# Humidifier.net
KiCad netlist of a schematic drawn in Altium Designer
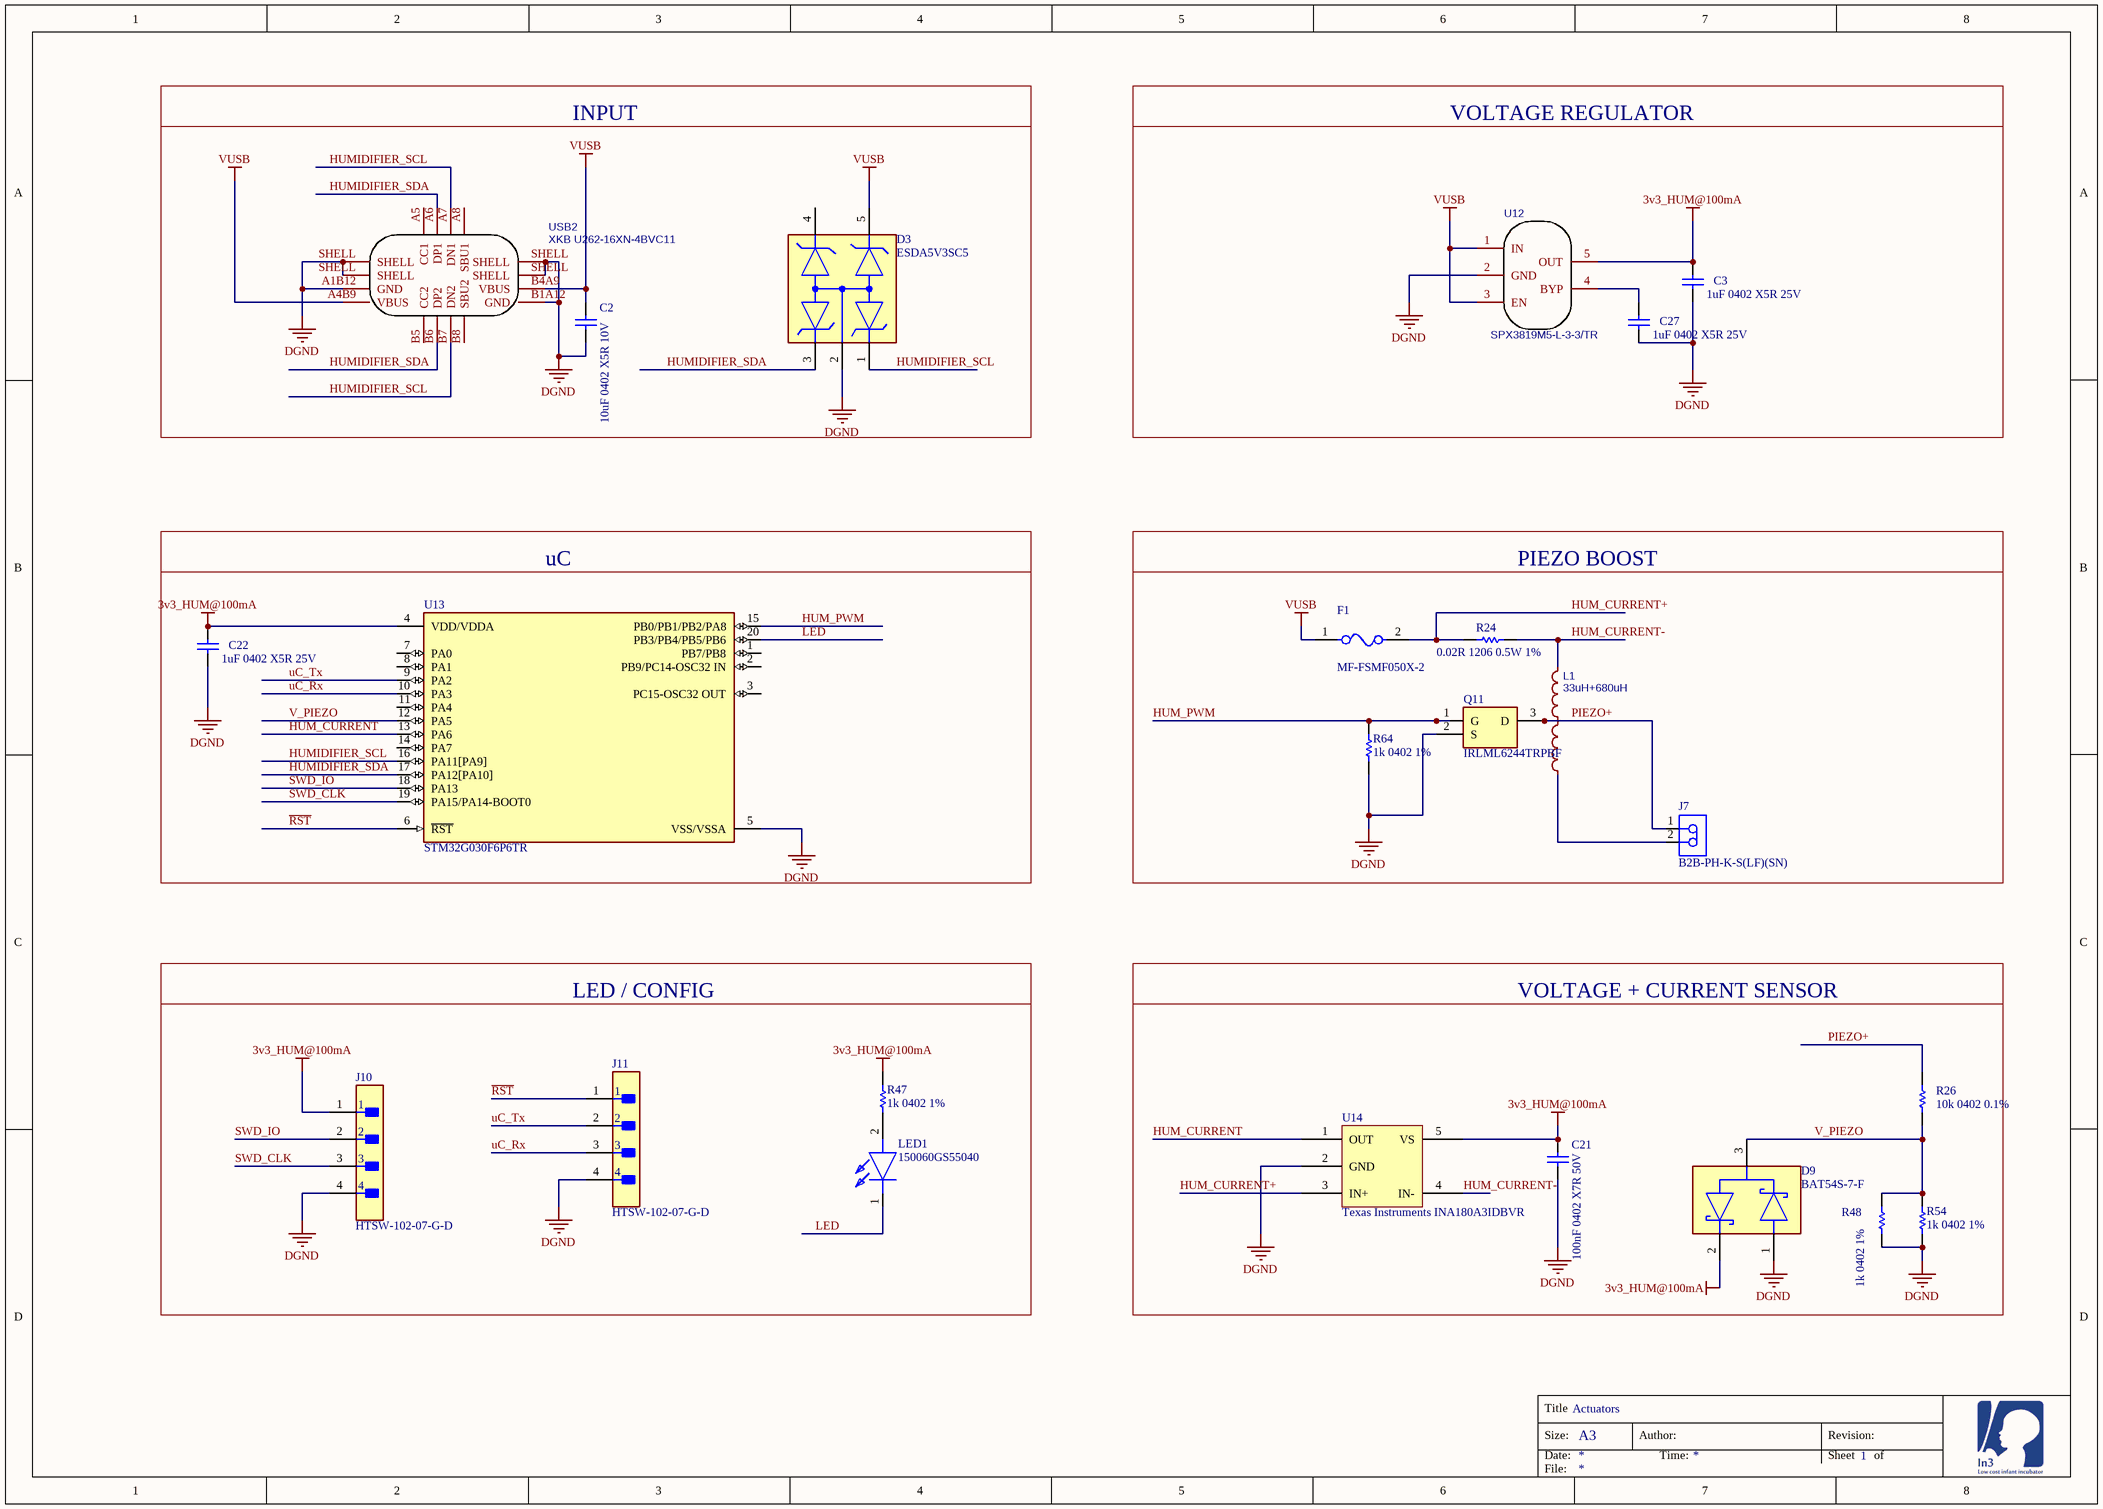
[diagram p0: Humidifier.SchDoc]

(export (version "E")
  (design (tool "Eeschema 10.0.6"))
  (components
    (comp (ref "C2")
      (value "10uF 0402 X5R 10V")
      (footprint "CAPC1005X55X25NL5T10")
      (libsource (lib "Altium Content Vault") (part "CAP-NP-2"))
    )
    (comp (ref "C3")
      (value "1uF 0402 X5R 25V")
      (footprint "CAPC1005X55X25NL5T10")
      (libsource (lib "Altium Content Vault") (part "CAP-NP-2"))
    )
    (comp (ref "C21")
      (value "100nF 0402 X7R 50V")
      (footprint "CAPC1005X55X25NL5T10")
      (libsource (lib "Altium Content Vault") (part "CAP-NP-2"))
    )
    (comp (ref "C22")
      (value "1uF 0402 X5R 25V")
      (footprint "CAPC1005X55X25NL5T10")
      (libsource (lib "Altium Content Vault") (part "CAP-NP-2"))
    )
    (comp (ref "C27")
      (value "1uF 0402 X5R 25V")
      (footprint "CAPC1005X55X25NL5T10")
      (libsource (lib "Altium Content Vault") (part "CAP-NP-2"))
    )
    (comp (ref "D3")
      (value "ESDA5V3SC5")
      (footprint "FP-SOT23-5L-MFG")
      (description "TVS DIODE 3V SOT23-5L")
      (fields
        (field (name "OCTOPART") "https://octopart.com/esda5v3sc5-stmicroelectronics-347709")
        (field (name "MANUFACTURER") "STMicroelectronics")
      )
      (libsource (lib "Altium Content Vault") (part "14b5e83594f4c3f2e89c011b5fb4f5e"))
    )
    (comp (ref "D9")
      (value "BAT54S-7-F")
      (footprint "FP-SOT23-MFG")
      (description "DIODE ARRAY SCHOTTKY 30V SOT23-3")
      (libsource (lib "Altium Content Vault") (part "835e4e71cf852b8cae3cf70bf14abf8"))
    )
    (comp (ref "F1")
      (value "MF-FSMF050X-2")
      (footprint "FP-MF-FSMF-MFG")
      (description "PTC RESET FUSE 6V 500MA 0603")
      (fields
        (field (name "MANUFACTURER") "Bourns Inc.")
        (field (name "OCTOPART") "https://octopart.com/mf-fsmf050x-2-bourns-10470804")
      )
      (libsource (lib "Altium Content Vault") (part "5bcf9b9f640e542cf0359d10258e979"))
    )
    (comp (ref "J7")
      (value "B2B-PH-K-S(LF)(SN)")
      (footprint "JST-B2B-PH-K-S_V")
      (fields (field (name "MANUFACTURER") "JST"))
      (libsource (lib "Altium Content Vault") (part "CN-2P-F-QF2"))
    )
    (comp (ref "J10")
      (value "HTSW-102-07-G-D")
      (footprint "FP-HTSW-102-07-G-D-MFG")
      (description "CONN HEADER VERT 4POS 2.54MM")
      (fields
        (field (name "MANUFACTURER") "Samtec")
        (field (name "OCTOPART") "https://octopart.com/htsw-102-07-g-d-samtec-10531767")
      )
      (libsource (lib "Altium Content Vault") (part "299a8cea1bdcbc3624fe62c390fa72c"))
    )
    (comp (ref "J11")
      (value "HTSW-102-07-G-D")
      (footprint "FP-HTSW-102-07-G-D-MFG")
      (description "CONN HEADER VERT 4POS 2.54MM")
      (fields
        (field (name "MANUFACTURER") "Samtec")
        (field (name "OCTOPART") "https://octopart.com/htsw-102-07-g-d-samtec-10531767")
      )
      (libsource (lib "Altium Content Vault") (part "299a8cea1bdcbc3624fe62c390fa72c"))
    )
    (comp (ref "L1")
      (value "33uH+680uH")
      (footprint "IND-THT_TRIPOD")
      (libsource (lib "LCSC") (part "tripod_inductor"))
    )
    (comp (ref "LED1")
      (value "150060GS55040")
      (footprint "SamacSys:LEDC1608X50N")
      (description "LED")
      (fields (field (name "MOUSER PART NUMBER") "710-150060GS55040"))
      (libsource (lib "*") (part "150060GS55040"))
    )
    (comp (ref "Q11")
      (value "IRLML6244TRPBF")
      (footprint "SOT95P237X112-3N")
      (description "Transistor")
      (fields (field (name "MOUSER PART NUMBER") "942-IRLML6244TRPBF"))
      (libsource (lib "in3ator") (part "IRLML6244TRPBF"))
    )
    (comp (ref "R24")
      (value "0.02R 1206 0.5W 1%")
      (footprint "CAPC3216X180X55ML20T25")
      (fields (field (name "MANUFACTURER PART NUMBER") "WSLP12065L000FEA") (field (name "POWER") "1W"))
      (libsource (lib "in3ator") (part "CMP-0abdc173b10ad57a-1"))
    )
    (comp (ref "R26")
      (value "10k 0402 0.1%")
      (footprint "RESC1005X40X25ML05T10")
      (libsource (lib "Altium Content Vault") (part "RES"))
    )
    (comp (ref "R47")
      (value "1k 0402 1%")
      (footprint "RESC1005X40X25ML05T10")
      (libsource (lib "Altium Content Vault") (part "RES"))
    )
    (comp (ref "R48")
      (value "1k 0402 1%")
      (footprint "RESC1005X40X25ML05T10")
      (libsource (lib "Altium Content Vault") (part "RES"))
    )
    (comp (ref "R54")
      (value "1k 0402 1%")
      (footprint "RESC1005X40X25ML05T10")
      (libsource (lib "Altium Content Vault") (part "RES"))
    )
    (comp (ref "R64")
      (value "1k 0402 1%")
      (footprint "RESC1005X40X25ML05T10")
      (libsource (lib "Altium Content Vault") (part "RES"))
    )
    (comp (ref "U12")
      (value "SPX3819M5-L-3-3/TR")
      (footprint "SOT-23-5_L3.0-W1.7-P0.95-LS2.8-BR")
      (fields (field (name "BOM_SUPPLIER PART") "C9055"))
      (libsource (lib "LCSC") (part "SPX3819M5-L-3-3/TR"))
    )
    (comp (ref "U13")
      (value "STM32G030F6P6TR")
      (footprint "FP-TSSOP20-YA-IPC_A")
      (description "IC MCU 32BIT 32KB FLASH 20TSSOP")
      (libsource (lib "Altium Content Vault") (part "be9f3bd3d72e89be6370f9e56c175d8"))
    )
    (comp (ref "U14")
      (value "Texas Instruments INA180A3IDBVR")
      (footprint "SOT23-5_D")
      (description "26V, Low- or High-Side Voltage Output Current Sense Amplifier 5-SOT-23 -40 to 125")
      (fields (field (name "MANUFACTURER PART NUMBER") "INA180A3IDBVR"))
      (libsource (lib "in3ator") (part "CMP-29d7e410373ef610-1"))
    )
    (comp (ref "USB2")
      (value "XKB U262-16XN-4BVC11")
      (footprint "U262-161N-4BVC11")
      (fields
        (field (name "BOM_SUPPLIER PART") "C319148")
        (field (name "BOM_MANUFACTURER PART") "U262-16XN-4BVC11")
        (field (name "CONTRIBUTOR") "LCSC")
      )
      (libsource (lib "LCSC") (part "XKB U262-16XN-4BVC11"))
    )
  )
  (nets
    (net (code "1") (name "/HUMIDIFIER_SCL") (class "Default")
      (node (ref "D3") (pin "1") (pinfunction "1_1") (pintype "passive"))
      (node (ref "U13") (pin "16") (pinfunction "PA11[PA9]_16") (pintype "bidirectional"))
      (node (ref "USB2") (pin "A7") (pinfunction "DN1_A7") (pintype "passive"))
      (node (ref "USB2") (pin "B7") (pinfunction "DN2_B7") (pintype "passive"))
    )
    (net (code "2") (name "/HUMIDIFIER_SDA") (class "Default")
      (node (ref "D3") (pin "3") (pinfunction "3_3") (pintype "passive"))
      (node (ref "U13") (pin "17") (pinfunction "PA12[PA10]_17") (pintype "bidirectional"))
      (node (ref "USB2") (pin "A6") (pinfunction "DP1_A6") (pintype "passive"))
      (node (ref "USB2") (pin "B6") (pinfunction "DP2_B6") (pintype "passive"))
    )
    (net (code "3") (name "/HUM_CURRENT") (class "Default")
      (node (ref "U13") (pin "13") (pinfunction "PA6_13") (pintype "bidirectional"))
      (node (ref "U14") (pin "1") (pinfunction "OUT_1") (pintype "passive"))
    )
    (net (code "4") (name "/HUM_CURRENT+") (class "Default")
      (node (ref "F1") (pin "2") (pinfunction "2_2") (pintype "passive"))
      (node (ref "R24") (pin "2") (pinfunction "2_2") (pintype "passive"))
      (node (ref "U14") (pin "3") (pinfunction "IN+_3") (pintype "passive"))
    )
    (net (code "5") (name "/HUM_CURRENT-") (class "Default")
      (node (ref "L1") (pin "3") (pinfunction "3_3") (pintype "passive"))
      (node (ref "R24") (pin "1") (pinfunction "1_1") (pintype "passive"))
      (node (ref "U14") (pin "4") (pinfunction "IN-_4") (pintype "passive"))
    )
    (net (code "6") (name "/HUM_PWM") (class "Default")
      (node (ref "Q11") (pin "1") (pinfunction "G_1") (pintype "passive"))
      (node (ref "R64") (pin "1") (pinfunction "1_1") (pintype "passive"))
      (node (ref "U13") (pin "15") (pinfunction "PB0/PB1/PB2/PA8_15") (pintype "bidirectional"))
    )
    (net (code "7") (name "/LED") (class "Default")
      (node (ref "LED1") (pin "1") (pinfunction "K_1") (pintype "passive"))
      (node (ref "U13") (pin "20") (pinfunction "PB3/PB4/PB5/PB6_20") (pintype "bidirectional"))
    )
    (net (code "8") (name "/PIEZO+") (class "Default")
      (node (ref "J7") (pin "1") (pinfunction "1_1") (pintype "passive"))
      (node (ref "L1") (pin "2") (pinfunction "2_2") (pintype "passive"))
      (node (ref "Q11") (pin "3") (pinfunction "D_3") (pintype "passive"))
      (node (ref "R26") (pin "2") (pinfunction "2_2") (pintype "passive"))
    )
    (net (code "9") (name "/SWD_CLK") (class "Default")
      (node (ref "J10") (pin "3") (pinfunction "3_3") (pintype "passive"))
      (node (ref "U13") (pin "19") (pinfunction "PA15/PA14-BOOT0_19") (pintype "bidirectional"))
    )
    (net (code "10") (name "/SWD_IO") (class "Default")
      (node (ref "J10") (pin "2") (pinfunction "2_2") (pintype "passive"))
      (node (ref "U13") (pin "18") (pinfunction "PA13_18") (pintype "bidirectional"))
    )
    (net (code "11") (name "/V_PIEZO") (class "Default")
      (node (ref "D9") (pin "3") (pinfunction "3_3") (pintype "passive"))
      (node (ref "R26") (pin "1") (pinfunction "1_1") (pintype "passive"))
      (node (ref "R48") (pin "1") (pinfunction "1_1") (pintype "passive"))
      (node (ref "R54") (pin "1") (pinfunction "1_1") (pintype "passive"))
      (node (ref "U13") (pin "12") (pinfunction "PA5_12") (pintype "bidirectional"))
    )
    (net (code "12") (name "/uC_Rx") (class "Default")
      (node (ref "J11") (pin "3") (pinfunction "3_3") (pintype "passive"))
      (node (ref "U13") (pin "10") (pinfunction "PA3_10") (pintype "bidirectional"))
    )
    (net (code "13") (name "/uC_Tx") (class "Default")
      (node (ref "J11") (pin "2") (pinfunction "2_2") (pintype "passive"))
      (node (ref "U13") (pin "9") (pinfunction "PA2_9") (pintype "bidirectional"))
    )
    (net (code "14") (name "/~{RST}") (class "Default")
      (node (ref "J11") (pin "1") (pinfunction "1_1") (pintype "passive"))
      (node (ref "U13") (pin "6") (pinfunction "~{RST}_6") (pintype "input"))
    )
    (net (code "15") (name "3v3_HUM@100mA") (class "Default")
      (node (ref "C21") (pin "2") (pinfunction "2_2") (pintype "passive"))
      (node (ref "C22") (pin "2") (pinfunction "2_2") (pintype "passive"))
      (node (ref "C3") (pin "2") (pinfunction "2_2") (pintype "passive"))
      (node (ref "D9") (pin "2") (pinfunction "2_2") (pintype "passive"))
      (node (ref "J10") (pin "1") (pinfunction "1_1") (pintype "passive"))
      (node (ref "R47") (pin "1") (pinfunction "1_1") (pintype "passive"))
      (node (ref "U12") (pin "5") (pinfunction "OUT_5") (pintype "passive"))
      (node (ref "U13") (pin "4") (pinfunction "VDD/VDDA_4") (pintype "power_in"))
      (node (ref "U14") (pin "5") (pinfunction "VS_5") (pintype "passive"))
    )
    (net (code "16") (name "DGND") (class "Default")
      (node (ref "C2") (pin "1") (pinfunction "1_1") (pintype "passive"))
      (node (ref "C21") (pin "1") (pinfunction "1_1") (pintype "passive"))
      (node (ref "C22") (pin "1") (pinfunction "1_1") (pintype "passive"))
      (node (ref "C27") (pin "1") (pinfunction "1_1") (pintype "passive"))
      (node (ref "C3") (pin "1") (pinfunction "1_1") (pintype "passive"))
      (node (ref "D3") (pin "2") (pinfunction "2_2") (pintype "passive"))
      (node (ref "D9") (pin "1") (pinfunction "1_1") (pintype "passive"))
      (node (ref "J10") (pin "4") (pinfunction "4_4") (pintype "passive"))
      (node (ref "J11") (pin "4") (pinfunction "4_4") (pintype "passive"))
      (node (ref "Q11") (pin "2") (pinfunction "S_2") (pintype "passive"))
      (node (ref "R48") (pin "2") (pinfunction "2_2") (pintype "passive"))
      (node (ref "R54") (pin "2") (pinfunction "2_2") (pintype "passive"))
      (node (ref "R64") (pin "2") (pinfunction "2_2") (pintype "passive"))
      (node (ref "U12") (pin "2") (pinfunction "GND_2") (pintype "passive"))
      (node (ref "U13") (pin "5") (pinfunction "VSS/VSSA_5") (pintype "power_in"))
      (node (ref "U14") (pin "2") (pinfunction "GND_2") (pintype "passive"))
      (node (ref "USB2") (pin "A1B12") (pinfunction "GND_A1B12") (pintype "passive"))
      (node (ref "USB2") (pin "B1A12") (pinfunction "GND_B1A12") (pintype "passive"))
      (node (ref "USB2") (pin "SHELL") (pinfunction "SHELL_SHELL") (pintype "passive"))
    )
    (net (code "17") (name "Net-(J7-Pad2)") (class "Default")
      (node (ref "J7") (pin "2") (pinfunction "2_2") (pintype "passive"))
      (node (ref "L1") (pin "1") (pinfunction "1_1") (pintype "passive"))
    )
    (net (code "18") (name "Net-(LED1-A)") (class "Default")
      (node (ref "LED1") (pin "2") (pinfunction "A_2") (pintype "passive"))
      (node (ref "R47") (pin "2") (pinfunction "2_2") (pintype "passive"))
    )
    (net (code "19") (name "Net-(U12-BYP)") (class "Default")
      (node (ref "C27") (pin "2") (pinfunction "2_2") (pintype "passive"))
      (node (ref "U12") (pin "4") (pinfunction "BYP_4") (pintype "passive"))
    )
    (net (code "20") (name "VUSB") (class "Default")
      (node (ref "C2") (pin "2") (pinfunction "2_2") (pintype "passive"))
      (node (ref "D3") (pin "5") (pinfunction "5_5") (pintype "passive"))
      (node (ref "F1") (pin "1") (pinfunction "1_1") (pintype "passive"))
      (node (ref "U12") (pin "1") (pinfunction "IN_1") (pintype "passive"))
      (node (ref "U12") (pin "3") (pinfunction "EN_3") (pintype "passive"))
      (node (ref "USB2") (pin "A4B9") (pinfunction "VBUS_A4B9") (pintype "passive"))
      (node (ref "USB2") (pin "B4A9") (pinfunction "VBUS_B4A9") (pintype "passive"))
    )
    (net (code "21") (name "unconnected-(D3-Pad4)") (class "Default")
      (node (ref "D3") (pin "4") (pinfunction "4_4") (pintype "passive"))
    )
    (net (code "22") (name "unconnected-(U13-PA0-Pad7)") (class "Default")
      (node (ref "U13") (pin "7") (pinfunction "PA0_7") (pintype "bidirectional"))
    )
    (net (code "23") (name "unconnected-(U13-PA1-Pad8)") (class "Default")
      (node (ref "U13") (pin "8") (pinfunction "PA1_8") (pintype "bidirectional"))
    )
    (net (code "24") (name "unconnected-(U13-PA4-Pad11)") (class "Default")
      (node (ref "U13") (pin "11") (pinfunction "PA4_11") (pintype "bidirectional"))
    )
    (net (code "25") (name "unconnected-(U13-PA7-Pad14)") (class "Default")
      (node (ref "U13") (pin "14") (pinfunction "PA7_14") (pintype "bidirectional"))
    )
    (net (code "26") (name "unconnected-(U13-PB7{slash}PB8-Pad1)") (class "Default")
      (node (ref "U13") (pin "1") (pinfunction "PB7/PB8_1") (pintype "bidirectional"))
    )
    (net (code "27") (name "unconnected-(U13-PB9{slash}PC14-OSC32_IN-Pad2)") (class "Default")
      (node (ref "U13") (pin "2") (pinfunction "PB9/PC14-OSC32_IN_2") (pintype "bidirectional"))
    )
    (net (code "28") (name "unconnected-(U13-PC15-OSC32_OUT-Pad3)") (class "Default")
      (node (ref "U13") (pin "3") (pinfunction "PC15-OSC32_OUT_3") (pintype "bidirectional"))
    )
    (net (code "29") (name "unconnected-(USB2-CC1-PadA5)") (class "Default")
      (node (ref "USB2") (pin "A5") (pinfunction "CC1_A5") (pintype "passive"))
    )
    (net (code "30") (name "unconnected-(USB2-CC2-PadB5)") (class "Default")
      (node (ref "USB2") (pin "B5") (pinfunction "CC2_B5") (pintype "passive"))
    )
    (net (code "31") (name "unconnected-(USB2-SBU1-PadA8)") (class "Default")
      (node (ref "USB2") (pin "A8") (pinfunction "SBU1_A8") (pintype "passive"))
    )
    (net (code "32") (name "unconnected-(USB2-SBU2-PadB8)") (class "Default")
      (node (ref "USB2") (pin "B8") (pinfunction "SBU2_B8") (pintype "passive"))
    )
  )
)
